# AMS_Control_2.net
KiCad netlist of a schematic drawn in Altium Designer
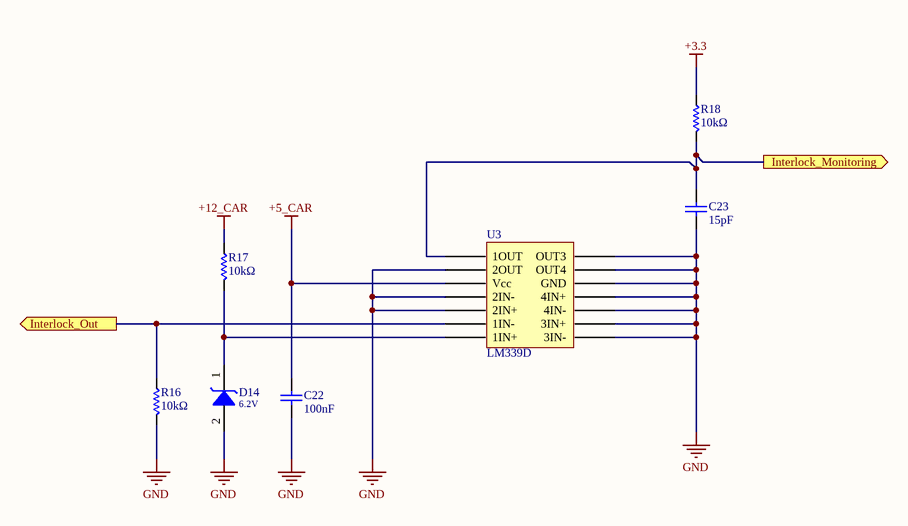
[diagram p0: AMS_Control_2.SchDoc]

(export (version "E")
  (design (tool "Eeschema 10.0.6"))
  (components
    (comp (ref "C22")
      (value "100nF")
      (footprint "0805_2x1.25x0.8mm_Reflow Soldering")
      (description "WCAP-CSGP Ceramic Capacitors, 0805, X7R, 50V, 100nF")
      (fields (field (name "PART NUMBER") "885012207098") (field (name "PUBLISHER") "Wurth Elektronik"))
      (libsource (lib "Components_Library") (part "885012207098"))
    )
    (comp (ref "C23")
      (value "15pF")
      (footprint "0805_2x1.25x0.6mm_Reflow Soldering")
      (description "WCAP-CSGP Ceramic Capacitors, 0805, NP0, 50V, 15pF")
      (fields (field (name "PART NUMBER") "885012007052") (field (name "PUBLISHER") "Wurth Elektronik"))
      (libsource (lib "Components_Library") (part "885012007052"))
    )
    (comp (ref "D14")
      (value "6.2V")
      (footprint "BZG05C-M-Series")
      (description "Zener Diode")
      (fields (field (name "MANUFACTURER") "Vishay"))
      (libsource (lib "Components_Library") (part "BZG05C6V2-E3-TR"))
    )
    (comp (ref "R16")
      (value "10kΩ")
      (footprint "CR0805")
      (description "Chip Resistor 0805")
      (fields (field (name "MANUFACTURER") "Bourns"))
      (libsource (lib "Components_Library") (part "CR0805-JW-103ELF"))
    )
    (comp (ref "R17")
      (value "10kΩ")
      (footprint "CR0805")
      (description "Chip Resistor 0805")
      (fields (field (name "MANUFACTURER") "Bourns"))
      (libsource (lib "Components_Library") (part "CR0805-JW-103ELF"))
    )
    (comp (ref "R18")
      (value "10kΩ")
      (footprint "CR0805")
      (description "Chip Resistor 0805")
      (fields (field (name "MANUFACTURER") "Bourns"))
      (libsource (lib "Components_Library") (part "CR0805-JW-103ELF"))
    )
    (comp (ref "U3")
      (value "LM339D")
      (footprint "LM339D")
      (description "Quad Differential\r\nComparators")
      (fields (field (name "MANUFACTURER") "Texas Instrument"))
      (libsource (lib "Components_Library") (part "LM339D"))
    )
  )
  (nets
    (net (code "1") (name "+3.3") (class "Default")
      (node (ref "R18") (pin "2") (pinfunction "2_2") (pintype "passive"))
    )
    (net (code "2") (name "+5_CAR") (class "Default")
      (node (ref "C22") (pin "2") (pinfunction "2_2") (pintype "passive"))
      (node (ref "U3") (pin "3") (pinfunction "Vcc_3") (pintype "passive"))
    )
    (net (code "3") (name "+12_CAR") (class "Default")
      (node (ref "R17") (pin "2") (pinfunction "2_2") (pintype "passive"))
    )
    (net (code "4") (name "/Interlock_Monitoring") (class "Default")
      (node (ref "C23") (pin "2") (pinfunction "2_2") (pintype "passive"))
      (node (ref "R18") (pin "1") (pinfunction "1_1") (pintype "passive"))
      (node (ref "U3") (pin "1") (pinfunction "1OUT_1") (pintype "passive"))
    )
    (net (code "5") (name "/Interlock_Out") (class "Default")
      (node (ref "R16") (pin "2") (pinfunction "2_2") (pintype "passive"))
      (node (ref "U3") (pin "6") (pinfunction "1IN-_6") (pintype "passive"))
    )
    (net (code "6") (name "GND") (class "Default")
      (node (ref "C22") (pin "1") (pinfunction "1_1") (pintype "passive"))
      (node (ref "C23") (pin "1") (pinfunction "1_1") (pintype "passive"))
      (node (ref "D14") (pin "2") (pinfunction "A_2") (pintype "passive"))
      (node (ref "R16") (pin "1") (pinfunction "1_1") (pintype "passive"))
      (node (ref "U3") (pin "10") (pinfunction "4IN-_10") (pintype "passive"))
      (node (ref "U3") (pin "11") (pinfunction "4IN+_11") (pintype "passive"))
      (node (ref "U3") (pin "12") (pinfunction "GND_12") (pintype "passive"))
      (node (ref "U3") (pin "13") (pinfunction "OUT4_13") (pintype "passive"))
      (node (ref "U3") (pin "14") (pinfunction "OUT3_14") (pintype "passive"))
      (node (ref "U3") (pin "2") (pinfunction "2OUT_2") (pintype "passive"))
      (node (ref "U3") (pin "4") (pinfunction "2IN-_4") (pintype "passive"))
      (node (ref "U3") (pin "5") (pinfunction "2IN+_5") (pintype "passive"))
      (node (ref "U3") (pin "8") (pinfunction "3IN-_8") (pintype "passive"))
      (node (ref "U3") (pin "9") (pinfunction "3IN+_9") (pintype "passive"))
    )
    (net (code "7") (name "Net-(D14-K)") (class "Default")
      (node (ref "D14") (pin "1") (pinfunction "K_1") (pintype "passive"))
      (node (ref "R17") (pin "1") (pinfunction "1_1") (pintype "passive"))
      (node (ref "U3") (pin "7") (pinfunction "1IN+_7") (pintype "passive"))
    )
  )
)
